# Project_A.net
KiCad netlist of a schematic drawn in Altium Designer
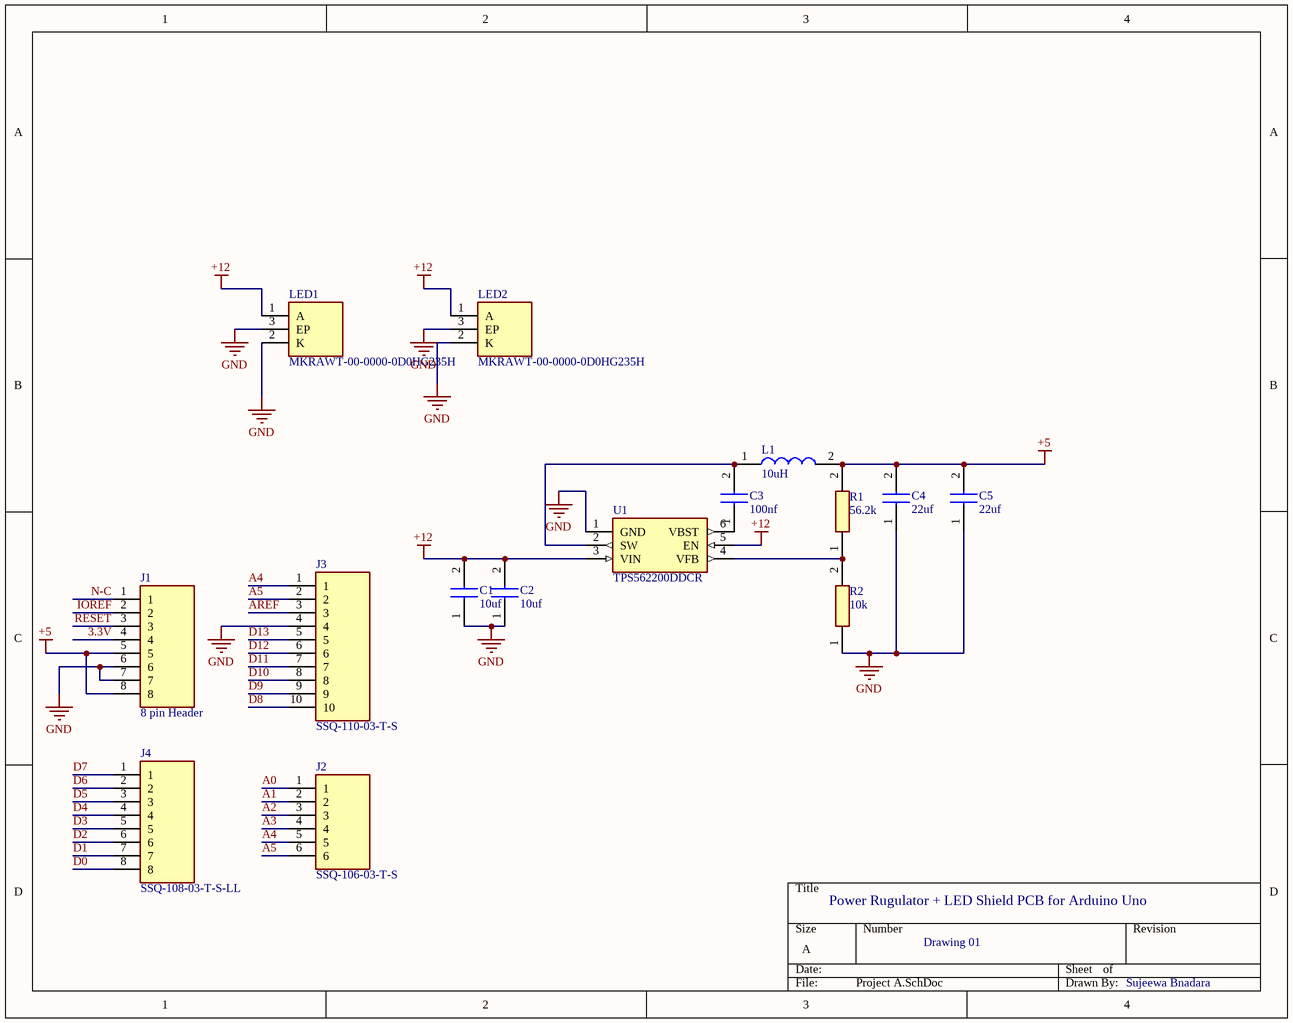
[diagram p0: Project A.SchDoc]

(export (version "E")
  (design (tool "Eeschema 10.0.6"))
  (components
    (comp (ref "C1")
      (value "10uf")
      (footprint "SamacSys:C2012_Commercial")
      (description "Capacitor")
      (fields
        (field (name "MANUFACTURER_PART_NUMBER") "C2012X5R1V106K085AC")
        (field (name "MOUSER PART NUMBER") "810-C2012X5R1V106K0C")
      )
      (libsource (lib "SamacSys") (part "C2012X5R1V106K085AC"))
    )
    (comp (ref "C2")
      (value "10uf")
      (footprint "SamacSys:C2012_Commercial")
      (description "Capacitor")
      (fields
        (field (name "MANUFACTURER_PART_NUMBER") "C2012X5R1V106K085AC")
        (field (name "MOUSER PART NUMBER") "810-C2012X5R1V106K0C")
      )
      (libsource (lib "SamacSys") (part "C2012X5R1V106K085AC"))
    )
    (comp (ref "C3")
      (value "100nf")
      (footprint "SamacSys:CAPC2012X94N")
      (description "Capacitor")
      (fields
        (field (name "MANUFACTURER_PART_NUMBER") "08053C104KAT2A")
        (field (name "MOUSER PART NUMBER") "581-08053C104K")
      )
      (libsource (lib "SamacSys") (part "08053C104KAT2A"))
    )
    (comp (ref "C4")
      (value "22uf")
      (footprint "SamacSys:CAPC1608X80N")
      (description "Capacitor")
      (fields
        (field (name "MANUFACTURER_PART_NUMBER") "C1608X5R1A226M080AC")
        (field (name "MOUSER PART NUMBER") "810-C1608X5R1A226M")
      )
      (libsource (lib "SamacSys") (part "C1608X5R1A226M080AC"))
    )
    (comp (ref "C5")
      (value "22uf")
      (footprint "SamacSys:CAPC1608X80N")
      (description "Capacitor")
      (fields
        (field (name "MANUFACTURER_PART_NUMBER") "C1608X5R1A226M080AC")
        (field (name "MOUSER PART NUMBER") "810-C1608X5R1A226M")
      )
      (libsource (lib "SamacSys") (part "C1608X5R1A226M080AC"))
    )
    (comp (ref "J1")
      (value "8 pin Header")
      (footprint "SamacSys:SSQ10803TSLL")
      (description "Connector")
      (fields
        (field (name "MANUFACTURER_PART_NUMBER") "SSQ-108-03-T-S-LL")
        (field (name "MOUSER PART NUMBER") "200-SSQ-108-03-TSLL")
      )
      (libsource (lib "*") (part "SSQ-108-03-T-S-LL"))
    )
    (comp (ref "J2")
      (value "SSQ-106-03-T-S")
      (footprint "SamacSys:RHDR6W64P254_1X6_1575X241X851P")
      (description "Connector")
      (fields (field (name "MOUSER PART NUMBER") "200-SSQ10603TS"))
      (libsource (lib "*") (part "SSQ-106-03-T-S"))
    )
    (comp (ref "J3")
      (value "SSQ-110-03-T-S")
      (footprint "SamacSys:RHDR10W64P254_1X10_2591X241X851P")
      (description "Connector")
      (fields (field (name "MOUSER PART NUMBER") "200-SSQ11003TS"))
      (libsource (lib "*") (part "SSQ-110-03-T-S"))
    )
    (comp (ref "J4")
      (value "SSQ-108-03-T-S-LL")
      (footprint "SamacSys:SSQ10803TSLL")
      (description "Connector")
      (fields (field (name "MOUSER PART NUMBER") "200-SSQ-108-03-TSLL"))
      (libsource (lib "*") (part "SSQ-108-03-T-S-LL"))
    )
    (comp (ref "L1")
      (value "10uH")
      (footprint "SamacSys:SRN6045_1")
      (description "Inductor")
      (fields
        (field (name "MANUFACTURER_PART_NUMBER") "SRN6045-4R7Y")
        (field (name "MOUSER PART NUMBER") "652-SRN6045-4R7Y")
      )
      (libsource (lib "SamacSys") (part "SRN6045-4R7Y"))
    )
    (comp (ref "LED1")
      (value "MKRAWT-00-0000-0D0HG235H")
      (footprint "SamacSys:MKRAWT0000000D0HG235H")
      (description "LED")
      (fields (field (name "MOUSER PART NUMBER") "941-MKRAWT0D0HG235H"))
      (libsource (lib "SamacSys") (part "MKRAWT-00-0000-0D0HG235H"))
    )
    (comp (ref "LED2")
      (value "MKRAWT-00-0000-0D0HG235H")
      (footprint "SamacSys:MKRAWT0000000D0HG235H")
      (description "LED")
      (fields (field (name "MOUSER PART NUMBER") "941-MKRAWT0D0HG235H"))
      (libsource (lib "SamacSys") (part "MKRAWT-00-0000-0D0HG235H"))
    )
    (comp (ref "R1")
      (value "56.2k")
      (footprint "SamacSys:RESC0603X26N")
      (description "Resistor")
      (fields
        (field (name "MANUFACTURER_PART_NUMBER") "RC0201FR-0756K2L")
        (field (name "MOUSER PART NUMBER") "603-RC0201FR-0756K2L")
      )
      (libsource (lib "SamacSys") (part "RC0201FR-0756K2L"))
    )
    (comp (ref "R2")
      (value "10k")
      (footprint "SamacSys:RESC0603X26N")
      (description "Resistor")
      (fields
        (field (name "MANUFACTURER_PART_NUMBER") "RC0201FR-0710KL")
        (field (name "MOUSER PART NUMBER") "603-RC0201FR-0710KL")
      )
      (libsource (lib "SamacSys") (part "RC0201FR-0710KL"))
    )
    (comp (ref "U1")
      (value "TPS562200DDCR")
      (footprint "SamacSys:SOT95P280X110-6N")
      (description "Undefined or Miscellaneous")
      (fields (field (name "MOUSER PART NUMBER") "595-TPS562200DDCR"))
      (libsource (lib "SamacSys") (part "TPS562200DDCR"))
    )
  )
  (nets
    (net (code "1") (name "+5") (class "Default")
      (node (ref "C4") (pin "2") (pinfunction "2_2") (pintype "passive"))
      (node (ref "C5") (pin "2") (pinfunction "2_2") (pintype "passive"))
      (node (ref "J1") (pin "5") (pinfunction "5_5") (pintype "passive"))
      (node (ref "J1") (pin "8") (pinfunction "8_8") (pintype "passive"))
      (node (ref "L1") (pin "2") (pinfunction "2_2") (pintype "passive"))
      (node (ref "R1") (pin "2") (pinfunction "2_2") (pintype "passive"))
    )
    (net (code "2") (name "+12") (class "Default")
      (node (ref "C1") (pin "2") (pinfunction "2_2") (pintype "passive"))
      (node (ref "C2") (pin "2") (pinfunction "2_2") (pintype "passive"))
      (node (ref "LED1") (pin "1") (pinfunction "A_1") (pintype "passive"))
      (node (ref "LED2") (pin "1") (pinfunction "A_1") (pintype "passive"))
      (node (ref "U1") (pin "3") (pinfunction "VIN_3") (pintype "input"))
      (node (ref "U1") (pin "5") (pinfunction "EN_5") (pintype "input"))
    )
    (net (code "3") (name "/3.3V") (class "Default")
      (node (ref "J1") (pin "4") (pinfunction "4_4") (pintype "passive"))
    )
    (net (code "4") (name "/A0") (class "Default")
      (node (ref "J2") (pin "1") (pinfunction "1_1") (pintype "passive"))
    )
    (net (code "5") (name "/A1") (class "Default")
      (node (ref "J2") (pin "2") (pinfunction "2_2") (pintype "passive"))
    )
    (net (code "6") (name "/A2") (class "Default")
      (node (ref "J2") (pin "3") (pinfunction "3_3") (pintype "passive"))
    )
    (net (code "7") (name "/A3") (class "Default")
      (node (ref "J2") (pin "4") (pinfunction "4_4") (pintype "passive"))
    )
    (net (code "8") (name "/A4") (class "Default")
      (node (ref "J2") (pin "5") (pinfunction "5_5") (pintype "passive"))
      (node (ref "J3") (pin "1") (pinfunction "1_1") (pintype "passive"))
    )
    (net (code "9") (name "/A5") (class "Default")
      (node (ref "J2") (pin "6") (pinfunction "6_6") (pintype "passive"))
      (node (ref "J3") (pin "2") (pinfunction "2_2") (pintype "passive"))
    )
    (net (code "10") (name "/AREF") (class "Default")
      (node (ref "J3") (pin "3") (pinfunction "3_3") (pintype "passive"))
    )
    (net (code "11") (name "/D0") (class "Default")
      (node (ref "J4") (pin "8") (pinfunction "8_8") (pintype "passive"))
    )
    (net (code "12") (name "/D1") (class "Default")
      (node (ref "J4") (pin "7") (pinfunction "7_7") (pintype "passive"))
    )
    (net (code "13") (name "/D2") (class "Default")
      (node (ref "J4") (pin "6") (pinfunction "6_6") (pintype "passive"))
    )
    (net (code "14") (name "/D3") (class "Default")
      (node (ref "J4") (pin "5") (pinfunction "5_5") (pintype "passive"))
    )
    (net (code "15") (name "/D4") (class "Default")
      (node (ref "J4") (pin "4") (pinfunction "4_4") (pintype "passive"))
    )
    (net (code "16") (name "/D5") (class "Default")
      (node (ref "J4") (pin "3") (pinfunction "3_3") (pintype "passive"))
    )
    (net (code "17") (name "/D6") (class "Default")
      (node (ref "J4") (pin "2") (pinfunction "2_2") (pintype "passive"))
    )
    (net (code "18") (name "/D7") (class "Default")
      (node (ref "J4") (pin "1") (pinfunction "1_1") (pintype "passive"))
    )
    (net (code "19") (name "/D8") (class "Default")
      (node (ref "J3") (pin "10") (pinfunction "10_10") (pintype "passive"))
    )
    (net (code "20") (name "/D9") (class "Default")
      (node (ref "J3") (pin "9") (pinfunction "9_9") (pintype "passive"))
    )
    (net (code "21") (name "/D10") (class "Default")
      (node (ref "J3") (pin "8") (pinfunction "8_8") (pintype "passive"))
    )
    (net (code "22") (name "/D11") (class "Default")
      (node (ref "J3") (pin "7") (pinfunction "7_7") (pintype "passive"))
    )
    (net (code "23") (name "/D12") (class "Default")
      (node (ref "J3") (pin "6") (pinfunction "6_6") (pintype "passive"))
    )
    (net (code "24") (name "/D13") (class "Default")
      (node (ref "J3") (pin "5") (pinfunction "5_5") (pintype "passive"))
    )
    (net (code "25") (name "/IOREF") (class "Default")
      (node (ref "J1") (pin "2") (pinfunction "2_2") (pintype "passive"))
    )
    (net (code "26") (name "/N-C") (class "Default")
      (node (ref "J1") (pin "1") (pinfunction "1_1") (pintype "passive"))
    )
    (net (code "27") (name "/RESET") (class "Default")
      (node (ref "J1") (pin "3") (pinfunction "3_3") (pintype "passive"))
    )
    (net (code "28") (name "GND") (class "Default")
      (node (ref "C1") (pin "1") (pinfunction "1_1") (pintype "passive"))
      (node (ref "C2") (pin "1") (pinfunction "1_1") (pintype "passive"))
      (node (ref "C4") (pin "1") (pinfunction "1_1") (pintype "passive"))
      (node (ref "C5") (pin "1") (pinfunction "1_1") (pintype "passive"))
      (node (ref "J1") (pin "6") (pinfunction "6_6") (pintype "passive"))
      (node (ref "J1") (pin "7") (pinfunction "7_7") (pintype "passive"))
      (node (ref "J3") (pin "4") (pinfunction "4_4") (pintype "passive"))
      (node (ref "LED1") (pin "2") (pinfunction "K_2") (pintype "passive"))
      (node (ref "LED1") (pin "3") (pinfunction "EP_3") (pintype "passive"))
      (node (ref "LED2") (pin "2") (pinfunction "K_2") (pintype "passive"))
      (node (ref "LED2") (pin "3") (pinfunction "EP_3") (pintype "passive"))
      (node (ref "R2") (pin "1") (pinfunction "1_1") (pintype "passive"))
      (node (ref "U1") (pin "1") (pinfunction "GND_1") (pintype "power_in"))
    )
    (net (code "29") (name "Net-(U1-SW)") (class "Default")
      (node (ref "C3") (pin "2") (pinfunction "2_2") (pintype "passive"))
      (node (ref "L1") (pin "1") (pinfunction "1_1") (pintype "passive"))
      (node (ref "U1") (pin "2") (pinfunction "SW_2") (pintype "output"))
    )
    (net (code "30") (name "Net-(U1-VBST)") (class "Default")
      (node (ref "C3") (pin "1") (pinfunction "1_1") (pintype "passive"))
      (node (ref "U1") (pin "6") (pinfunction "VBST_6") (pintype "output"))
    )
    (net (code "31") (name "Net-(U1-VFB)") (class "Default")
      (node (ref "R1") (pin "1") (pinfunction "1_1") (pintype "passive"))
      (node (ref "R2") (pin "2") (pinfunction "2_2") (pintype "passive"))
      (node (ref "U1") (pin "4") (pinfunction "VFB_4") (pintype "output"))
    )
  )
)
